# rpi-psu.net
KiCad netlist of a schematic drawn in EAGLE
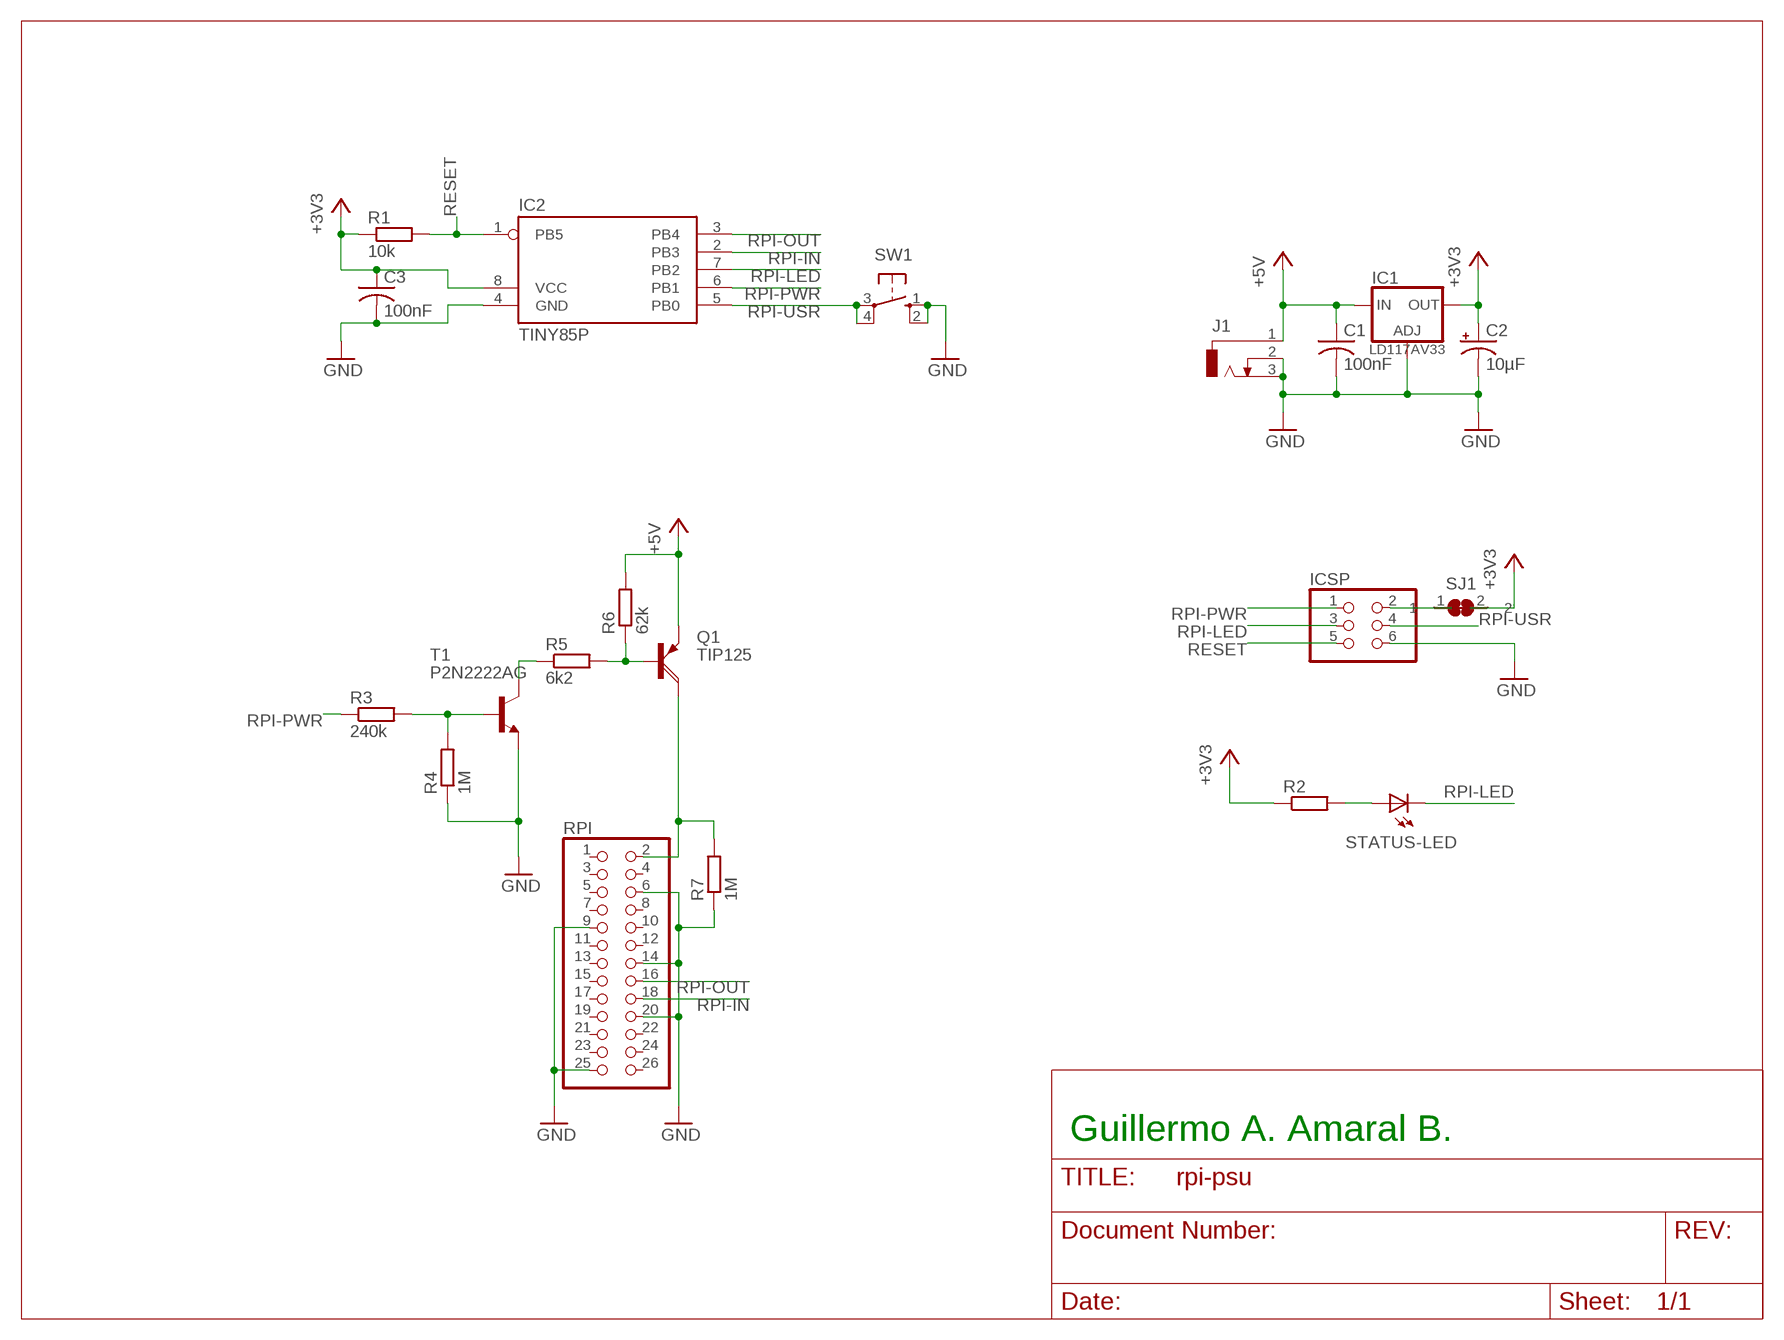
[diagram p0: schematic, sheet 1]

(export (version "E")
  (design (tool "Eeschema 10.0.6"))
  (components
    (comp (ref "C1")
      (value "100nF")
      (footprint "eagle-import:C050-024X044")
      (libsource (lib "eagle-import") (part "C-US050-024X044"))
    )
    (comp (ref "C2")
      (value "10µF")
      (footprint "eagle-import:E2,5-6E")
      (libsource (lib "eagle-import") (part "CPOL-USE2,5-6E"))
    )
    (comp (ref "C3")
      (value "100nF")
      (footprint "eagle-import:C050-024X044")
      (libsource (lib "eagle-import") (part "C-US050-024X044"))
    )
    (comp (ref "IC1")
      (value "LD117AV33")
      (footprint "eagle-import:TO220L1")
      (libsource (lib "eagle-import") (part "LD117A?V33"))
    )
    (comp (ref "IC2")
      (value "TINY85P")
      (footprint "eagle-import:DIL08")
      (libsource (lib "eagle-import") (part "TINY85P"))
    )
    (comp (ref "ICSP")
      (value "PINHD-2X3")
      (footprint "eagle-import:2X03")
      (libsource (lib "eagle-import") (part "PINHD-2X3"))
    )
    (comp (ref "J1")
      (value "DCJ0303")
      (footprint "eagle-import:DCJ0303")
      (libsource (lib "eagle-import") (part "DCJ0303"))
    )
    (comp (ref "Q1")
      (value "TIP125")
      (footprint "eagle-import:TO220AH")
      (libsource (lib "eagle-import") (part "TIP125"))
    )
    (comp (ref "R1")
      (value "10k")
      (footprint "eagle-import:0207_10")
      (libsource (lib "eagle-import") (part "R-EU_0207/10"))
    )
    (comp (ref "R2")
      (value "R-EU_0207/10")
      (footprint "eagle-import:0207_10")
      (libsource (lib "eagle-import") (part "R-EU_0207/10"))
    )
    (comp (ref "R3")
      (value "240k")
      (footprint "eagle-import:0207_10")
      (libsource (lib "eagle-import") (part "R-EU_0207/10"))
    )
    (comp (ref "R4")
      (value "1M")
      (footprint "eagle-import:0207_10")
      (libsource (lib "eagle-import") (part "R-EU_0207/10"))
    )
    (comp (ref "R5")
      (value "6k2")
      (footprint "eagle-import:0207_10")
      (libsource (lib "eagle-import") (part "R-EU_0207/10"))
    )
    (comp (ref "R6")
      (value "62k")
      (footprint "eagle-import:0207_10")
      (libsource (lib "eagle-import") (part "R-EU_0207/10"))
    )
    (comp (ref "R7")
      (value "1M")
      (footprint "eagle-import:0207_10")
      (libsource (lib "eagle-import") (part "R-EU_0207/10"))
    )
    (comp (ref "RPI")
      (value "PINHD-2X13")
      (footprint "eagle-import:2X13")
      (libsource (lib "eagle-import") (part "PINHD-2X13"))
    )
    (comp (ref "SJ1")
      (value "SJ-BRIDGED")
      (footprint "eagle-import:SJ-BRIDGED")
      (libsource (lib "eagle-import") (part "SJ-BRIDGED"))
    )
    (comp (ref "STATUS-LED")
      (value "LED5MM")
      (footprint "eagle-import:LED5MM")
      (libsource (lib "eagle-import") (part "LED5MM"))
    )
    (comp (ref "SW1")
      (value "10-XX")
      (footprint "eagle-import:B3F-10XX")
      (fields (field (name "MPN") "B3F-1000"))
      (libsource (lib "eagle-import") (part "10-XX"))
    )
    (comp (ref "T1")
      (value "P2N2222AG")
      (footprint "eagle-import:TO92")
      (libsource (lib "eagle-import") (part "2N3904"))
    )
  )
  (nets
    (net (code "1") (name "+3V3") (class "Default")
      (node (ref "C2") (pin "+") (pinfunction "+_+") (pintype "passive"))
      (node (ref "C3") (pin "1") (pinfunction "1_1") (pintype "passive"))
      (node (ref "IC1") (pin "2") (pinfunction "OUT_2") (pintype "passive"))
      (node (ref "IC2") (pin "8") (pinfunction "VCC_8") (pintype "power_in"))
      (node (ref "R1") (pin "1") (pinfunction "1_1") (pintype "passive"))
      (node (ref "R2") (pin "1") (pinfunction "1_1") (pintype "passive"))
      (node (ref "SJ1") (pin "2") (pinfunction "2_2") (pintype "bidirectional"))
    )
    (net (code "2") (name "+5V") (class "Default")
      (node (ref "C1") (pin "1") (pinfunction "1_1") (pintype "passive"))
      (node (ref "IC1") (pin "3") (pinfunction "IN_3") (pintype "input"))
      (node (ref "J1") (pin "1") (pinfunction "1_1") (pintype "passive"))
      (node (ref "Q1") (pin "E") (pinfunction "E_E") (pintype "passive"))
      (node (ref "R6") (pin "2") (pinfunction "2_2") (pintype "passive"))
    )
    (net (code "3") (name "/RESET") (class "Default")
      (node (ref "IC2") (pin "1") (pinfunction "PB5_1") (pintype "bidirectional"))
      (node (ref "ICSP") (pin "5") (pinfunction "5_5") (pintype "passive"))
      (node (ref "R1") (pin "2") (pinfunction "2_2") (pintype "passive"))
    )
    (net (code "4") (name "/RPI-IN") (class "Default")
      (node (ref "IC2") (pin "2") (pinfunction "PB3_2") (pintype "bidirectional"))
      (node (ref "RPI") (pin "18") (pinfunction "18_18") (pintype "passive"))
    )
    (net (code "5") (name "/RPI-LED") (class "Default")
      (node (ref "IC2") (pin "7") (pinfunction "PB2_7") (pintype "bidirectional"))
      (node (ref "ICSP") (pin "3") (pinfunction "3_3") (pintype "passive"))
      (node (ref "STATUS-LED") (pin "K") (pinfunction "C_K") (pintype "passive"))
    )
    (net (code "6") (name "/RPI-OUT") (class "Default")
      (node (ref "IC2") (pin "3") (pinfunction "PB4_3") (pintype "bidirectional"))
      (node (ref "RPI") (pin "16") (pinfunction "16_16") (pintype "passive"))
    )
    (net (code "7") (name "/RPI-PWR") (class "Default")
      (node (ref "IC2") (pin "6") (pinfunction "PB1_6") (pintype "bidirectional"))
      (node (ref "ICSP") (pin "1") (pinfunction "1_1") (pintype "passive"))
      (node (ref "R3") (pin "1") (pinfunction "1_1") (pintype "passive"))
    )
    (net (code "8") (name "/RPI-USR") (class "Default")
      (node (ref "IC2") (pin "5") (pinfunction "PB0_5") (pintype "bidirectional"))
      (node (ref "ICSP") (pin "4") (pinfunction "4_4") (pintype "passive"))
      (node (ref "SW1") (pin "3") (pinfunction "P_3") (pintype "passive"))
      (node (ref "SW1") (pin "4") (pinfunction "P1_4") (pintype "passive"))
    )
    (net (code "9") (name "GND") (class "Default")
      (node (ref "C1") (pin "2") (pinfunction "2_2") (pintype "passive"))
      (node (ref "C2") (pin "-") (pinfunction "-_-") (pintype "passive"))
      (node (ref "C3") (pin "2") (pinfunction "2_2") (pintype "passive"))
      (node (ref "IC1") (pin "1") (pinfunction "ADJ_1") (pintype "input"))
      (node (ref "IC2") (pin "4") (pinfunction "GND_4") (pintype "power_in"))
      (node (ref "ICSP") (pin "6") (pinfunction "6_6") (pintype "passive"))
      (node (ref "J1") (pin "2") (pinfunction "2_2") (pintype "passive"))
      (node (ref "J1") (pin "3") (pinfunction "3_3") (pintype "passive"))
      (node (ref "R4") (pin "1") (pinfunction "1_1") (pintype "passive"))
      (node (ref "R7") (pin "1") (pinfunction "1_1") (pintype "passive"))
      (node (ref "RPI") (pin "14") (pinfunction "14_14") (pintype "passive"))
      (node (ref "RPI") (pin "20") (pinfunction "20_20") (pintype "passive"))
      (node (ref "RPI") (pin "25") (pinfunction "25_25") (pintype "passive"))
      (node (ref "RPI") (pin "6") (pinfunction "6_6") (pintype "passive"))
      (node (ref "RPI") (pin "9") (pinfunction "9_9") (pintype "passive"))
      (node (ref "SW1") (pin "1") (pinfunction "S_1") (pintype "passive"))
      (node (ref "SW1") (pin "2") (pinfunction "S1_2") (pintype "passive"))
      (node (ref "T1") (pin "3") (pinfunction "E_3") (pintype "passive"))
    )
    (net (code "10") (name "Net-(ICSP-Pad2)") (class "Default")
      (node (ref "ICSP") (pin "2") (pinfunction "2_2") (pintype "passive"))
      (node (ref "SJ1") (pin "1") (pinfunction "1_1") (pintype "bidirectional"))
    )
    (net (code "11") (name "Net-(Q1-PadB)") (class "Default")
      (node (ref "Q1") (pin "B") (pinfunction "B_B") (pintype "passive"))
      (node (ref "R5") (pin "2") (pinfunction "2_2") (pintype "passive"))
      (node (ref "R6") (pin "1") (pinfunction "1_1") (pintype "passive"))
    )
    (net (code "12") (name "Net-(Q1-PadC)") (class "Default")
      (node (ref "Q1") (pin "C") (pinfunction "C_C") (pintype "passive"))
      (node (ref "R7") (pin "2") (pinfunction "2_2") (pintype "passive"))
      (node (ref "RPI") (pin "2") (pinfunction "2_2") (pintype "passive"))
    )
    (net (code "13") (name "Net-(R2-Pad2)") (class "Default")
      (node (ref "R2") (pin "2") (pinfunction "2_2") (pintype "passive"))
      (node (ref "STATUS-LED") (pin "A") (pinfunction "A_A") (pintype "passive"))
    )
    (net (code "14") (name "Net-(T1-B)") (class "Default")
      (node (ref "R3") (pin "2") (pinfunction "2_2") (pintype "passive"))
      (node (ref "R4") (pin "2") (pinfunction "2_2") (pintype "passive"))
      (node (ref "T1") (pin "2") (pinfunction "B_2") (pintype "passive"))
    )
    (net (code "15") (name "Net-(T1-C)") (class "Default")
      (node (ref "R5") (pin "1") (pinfunction "1_1") (pintype "passive"))
      (node (ref "T1") (pin "1") (pinfunction "C_1") (pintype "passive"))
    )
    (net (code "16") (name "unconnected-(RPI-Pad1)") (class "Default")
      (node (ref "RPI") (pin "1") (pinfunction "1_1") (pintype "passive"))
    )
    (net (code "17") (name "unconnected-(RPI-Pad3)") (class "Default")
      (node (ref "RPI") (pin "3") (pinfunction "3_3") (pintype "passive"))
    )
    (net (code "18") (name "unconnected-(RPI-Pad4)") (class "Default")
      (node (ref "RPI") (pin "4") (pinfunction "4_4") (pintype "passive"))
    )
    (net (code "19") (name "unconnected-(RPI-Pad5)") (class "Default")
      (node (ref "RPI") (pin "5") (pinfunction "5_5") (pintype "passive"))
    )
    (net (code "20") (name "unconnected-(RPI-Pad7)") (class "Default")
      (node (ref "RPI") (pin "7") (pinfunction "7_7") (pintype "passive"))
    )
    (net (code "21") (name "unconnected-(RPI-Pad8)") (class "Default")
      (node (ref "RPI") (pin "8") (pinfunction "8_8") (pintype "passive"))
    )
    (net (code "22") (name "unconnected-(RPI-Pad10)") (class "Default")
      (node (ref "RPI") (pin "10") (pinfunction "10_10") (pintype "passive"))
    )
    (net (code "23") (name "unconnected-(RPI-Pad11)") (class "Default")
      (node (ref "RPI") (pin "11") (pinfunction "11_11") (pintype "passive"))
    )
    (net (code "24") (name "unconnected-(RPI-Pad12)") (class "Default")
      (node (ref "RPI") (pin "12") (pinfunction "12_12") (pintype "passive"))
    )
    (net (code "25") (name "unconnected-(RPI-Pad13)") (class "Default")
      (node (ref "RPI") (pin "13") (pinfunction "13_13") (pintype "passive"))
    )
    (net (code "26") (name "unconnected-(RPI-Pad15)") (class "Default")
      (node (ref "RPI") (pin "15") (pinfunction "15_15") (pintype "passive"))
    )
    (net (code "27") (name "unconnected-(RPI-Pad17)") (class "Default")
      (node (ref "RPI") (pin "17") (pinfunction "17_17") (pintype "passive"))
    )
    (net (code "28") (name "unconnected-(RPI-Pad19)") (class "Default")
      (node (ref "RPI") (pin "19") (pinfunction "19_19") (pintype "passive"))
    )
    (net (code "29") (name "unconnected-(RPI-Pad21)") (class "Default")
      (node (ref "RPI") (pin "21") (pinfunction "21_21") (pintype "passive"))
    )
    (net (code "30") (name "unconnected-(RPI-Pad22)") (class "Default")
      (node (ref "RPI") (pin "22") (pinfunction "22_22") (pintype "passive"))
    )
    (net (code "31") (name "unconnected-(RPI-Pad23)") (class "Default")
      (node (ref "RPI") (pin "23") (pinfunction "23_23") (pintype "passive"))
    )
    (net (code "32") (name "unconnected-(RPI-Pad24)") (class "Default")
      (node (ref "RPI") (pin "24") (pinfunction "24_24") (pintype "passive"))
    )
    (net (code "33") (name "unconnected-(RPI-Pad26)") (class "Default")
      (node (ref "RPI") (pin "26") (pinfunction "26_26") (pintype "passive"))
    )
  )
)
